# SmartSwitch_V1_1.net
KiCad netlist of a schematic drawn in EAGLE
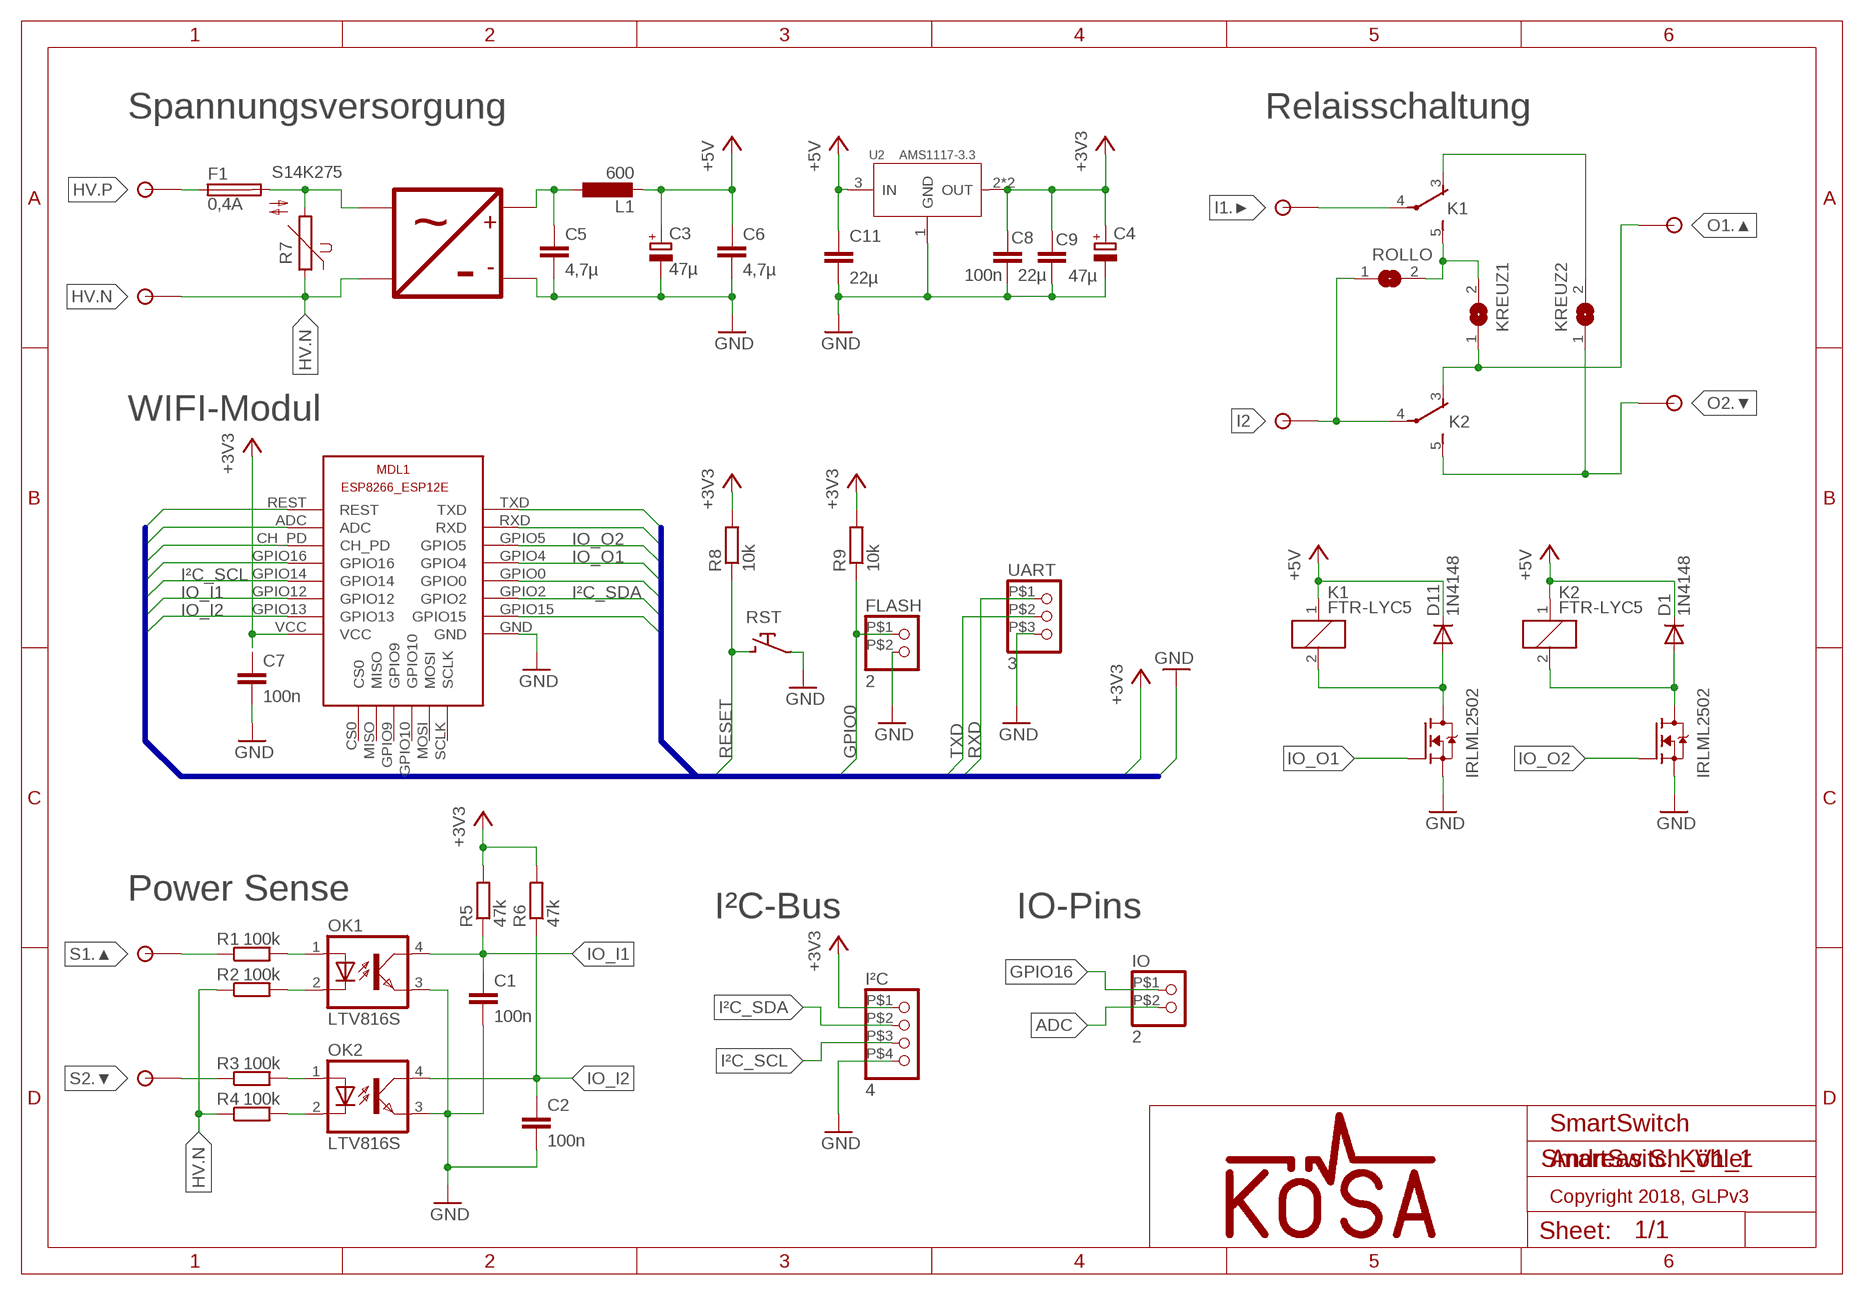
[diagram p0: schematic, sheet 1]

(export (version "E")
  (design (tool "Eeschema 10.0.6"))
  (components
    (comp (ref "C1")
      (value "100n")
      (footprint "eagle-import:C0805")
      (libsource (lib "eagle-import") (part "C-EUC0805"))
    )
    (comp (ref "C2")
      (value "100n")
      (footprint "eagle-import:C0805")
      (libsource (lib "eagle-import") (part "C-EUC0805"))
    )
    (comp (ref "C3")
      (value "47µ")
      (footprint "eagle-import:E2-5")
      (libsource (lib "eagle-import") (part "CPOL-EUE2-5"))
    )
    (comp (ref "C4")
      (value "47µ")
      (footprint "eagle-import:E2-5")
      (libsource (lib "eagle-import") (part "CPOL-EUE2-5"))
    )
    (comp (ref "C5")
      (value "4,7µ")
      (footprint "eagle-import:C0805")
      (libsource (lib "eagle-import") (part "C-EUC0805"))
    )
    (comp (ref "C6")
      (value "4,7µ")
      (footprint "eagle-import:C0805")
      (libsource (lib "eagle-import") (part "C-EUC0805"))
    )
    (comp (ref "C7")
      (value "100n")
      (footprint "eagle-import:C0805")
      (libsource (lib "eagle-import") (part "C-EUC0805"))
    )
    (comp (ref "C8")
      (value "100n")
      (footprint "eagle-import:C0805")
      (libsource (lib "eagle-import") (part "C-EUC0805"))
    )
    (comp (ref "C9")
      (value "22µ")
      (footprint "eagle-import:C0805")
      (libsource (lib "eagle-import") (part "C-EUC0805"))
    )
    (comp (ref "C11")
      (value "22µ")
      (footprint "eagle-import:C0805")
      (libsource (lib "eagle-import") (part "C-EUC0805"))
    )
    (comp (ref "D1")
      (value "1N4148")
      (footprint "eagle-import:SOD323-W")
      (libsource (lib "eagle-import") (part "DIODE-SOD323-W"))
    )
    (comp (ref "D11")
      (value "1N4148")
      (footprint "eagle-import:SOD323-W")
      (libsource (lib "eagle-import") (part "DIODE-SOD323-W"))
    )
    (comp (ref "F1")
      (value "0,4A")
      (footprint "eagle-import:SMD_FUSE_HOLDER")
      (libsource (lib "eagle-import") (part "SMD_FUSE_HOLDER"))
    )
    (comp (ref "FLASH")
      (value "2")
      (footprint "eagle-import:1X02_SMALL")
      (libsource (lib "eagle-import") (part "PINHD-1X2SMALL"))
    )
    (comp (ref "IO")
      (value "2")
      (footprint "eagle-import:1X02_SMALL")
      (libsource (lib "eagle-import") (part "PINHD-1X2SMALL"))
    )
    (comp (ref "I²C")
      (value "4")
      (footprint "eagle-import:1X04_SMALL")
      (libsource (lib "eagle-import") (part "PINHD-1X4SMALL"))
    )
    (comp (ref "K1")
      (value "FTR-LYC5")
      (footprint "eagle-import:FTR-LYC")
      (libsource (lib "eagle-import") (part "FTR-LYC5"))
    )
    (comp (ref "K2")
      (value "FTR-LYC5")
      (footprint "eagle-import:FTR-LYC")
      (libsource (lib "eagle-import") (part "FTR-LYC5"))
    )
    (comp (ref "KREUZ1")
      (value "SJW")
      (footprint "eagle-import:SJW")
      (libsource (lib "eagle-import") (part "SJW"))
    )
    (comp (ref "KREUZ2")
      (value "SJW")
      (footprint "eagle-import:SJW")
      (libsource (lib "eagle-import") (part "SJW"))
    )
    (comp (ref "L1")
      (value "600")
      (footprint "eagle-import:L3225P")
      (libsource (lib "eagle-import") (part "L-EUL3225P"))
    )
    (comp (ref "MDL1")
      (value "1")
      (footprint "eagle-import:ESP8266-ESP12E")
      (libsource (lib "eagle-import") (part "ESP8266-12EESP8266-ESP12E"))
    )
    (comp (ref "OK1")
      (value "LTV816S")
      (footprint "eagle-import:SMD4")
      (libsource (lib "eagle-import") (part "LTV816S"))
    )
    (comp (ref "OK2")
      (value "LTV816S")
      (footprint "eagle-import:SMD4")
      (libsource (lib "eagle-import") (part "LTV816S"))
    )
    (comp (ref "R1")
      (value "100k")
      (footprint "eagle-import:R1206")
      (libsource (lib "eagle-import") (part "R-EU_R1206"))
    )
    (comp (ref "R2")
      (value "100k")
      (footprint "eagle-import:R1206")
      (libsource (lib "eagle-import") (part "R-EU_R1206"))
    )
    (comp (ref "R3")
      (value "100k")
      (footprint "eagle-import:R1206")
      (libsource (lib "eagle-import") (part "R-EU_R1206"))
    )
    (comp (ref "R4")
      (value "100k")
      (footprint "eagle-import:R1206")
      (libsource (lib "eagle-import") (part "R-EU_R1206"))
    )
    (comp (ref "R5")
      (value "47k")
      (footprint "eagle-import:R1206")
      (libsource (lib "eagle-import") (part "R-EU_R1206"))
    )
    (comp (ref "R6")
      (value "47k")
      (footprint "eagle-import:R1206")
      (libsource (lib "eagle-import") (part "R-EU_R1206"))
    )
    (comp (ref "R7")
      (value "S14K275")
      (footprint "eagle-import:S14K275")
      (libsource (lib "eagle-import") (part "S14K275"))
    )
    (comp (ref "R8")
      (value "10k")
      (footprint "eagle-import:R1206")
      (libsource (lib "eagle-import") (part "R-EU_R1206"))
    )
    (comp (ref "R9")
      (value "10k")
      (footprint "eagle-import:R1206")
      (libsource (lib "eagle-import") (part "R-EU_R1206"))
    )
    (comp (ref "ROLLO")
      (value "SJW")
      (footprint "eagle-import:SJW")
      (libsource (lib "eagle-import") (part "SJW"))
    )
    (comp (ref "RST")
      (value "SMD-TASTER_REICHELT_KMR_231_G_LFS")
      (footprint "eagle-import:SMD-TASTER_REICHELT_KMR_231_G_LFS")
      (libsource (lib "eagle-import") (part "SMD-TASTER_REICHELT_KMR_231_G_LFS"))
    )
    (comp (ref "U$1")
      (value "HLK-PM01")
      (footprint "eagle-import:HLK-PM01")
      (libsource (lib "eagle-import") (part "HLK-PM01"))
    )
    (comp (ref "U$2")
      (value "RND_205-00276")
      (footprint "eagle-import:RND205-00276")
      (libsource (lib "eagle-import") (part "RND_205-00276"))
    )
    (comp (ref "U$3")
      (value "RND_205-00276")
      (footprint "eagle-import:RND205-00276")
      (libsource (lib "eagle-import") (part "RND_205-00276"))
    )
    (comp (ref "U$4")
      (value "RND_205-00276")
      (footprint "eagle-import:RND205-00276")
      (libsource (lib "eagle-import") (part "RND_205-00276"))
    )
    (comp (ref "U$5")
      (value "RND_205-00276")
      (footprint "eagle-import:RND205-00276")
      (libsource (lib "eagle-import") (part "RND_205-00276"))
    )
    (comp (ref "U$7")
      (value "IRLML2502")
      (footprint "eagle-import:SOT23")
      (libsource (lib "eagle-import") (part "IRLML2502"))
    )
    (comp (ref "U$8")
      (value "IRLML2502")
      (footprint "eagle-import:SOT23")
      (libsource (lib "eagle-import") (part "IRLML2502"))
    )
    (comp (ref "U2")
      (value "AMS1117-3.3")
      (footprint "eagle-import:SOT-223")
      (fields (field (name "MPN") "CJT1117-3.3"))
      (libsource (lib "eagle-import") (part "PMIC-CJT1117-3.3(SOT223)"))
    )
    (comp (ref "UART")
      (value "3")
      (footprint "eagle-import:1X03_SMALL")
      (libsource (lib "eagle-import") (part "PINHD-1X3SMALL"))
    )
  )
  (nets
    (net (code "1") (name "+3V3") (class "Default")
      (node (ref "C4") (pin "+") (pinfunction "+_+") (pintype "passive"))
      (node (ref "C7") (pin "1") (pinfunction "1_1") (pintype "passive"))
      (node (ref "C8") (pin "1") (pinfunction "1_1") (pintype "passive"))
      (node (ref "C9") (pin "1") (pinfunction "1_1") (pintype "passive"))
      (node (ref "I²C") (pin "P$1") (pinfunction "1_P$1") (pintype "passive"))
      (node (ref "MDL1") (pin "CH_PD") (pinfunction "CH_PD_CH_PD") (pintype "bidirectional"))
      (node (ref "MDL1") (pin "VCC") (pinfunction "VCC_VCC") (pintype "bidirectional"))
      (node (ref "R5") (pin "2") (pinfunction "2_2") (pintype "passive"))
      (node (ref "R6") (pin "2") (pinfunction "2_2") (pintype "passive"))
      (node (ref "R8") (pin "2") (pinfunction "2_2") (pintype "passive"))
      (node (ref "R9") (pin "2") (pinfunction "2_2") (pintype "passive"))
      (node (ref "U2") (pin "2") (pinfunction "OUT_2") (pintype "bidirectional"))
      (node (ref "U2") (pin "TER") (pinfunction "OUT_TER") (pintype "bidirectional"))
    )
    (net (code "2") (name "+5V") (class "Default")
      (node (ref "C11") (pin "1") (pinfunction "1_1") (pintype "passive"))
      (node (ref "C3") (pin "+") (pinfunction "+_+") (pintype "passive"))
      (node (ref "C6") (pin "1") (pinfunction "1_1") (pintype "passive"))
      (node (ref "D1") (pin "C") (pinfunction "C_C") (pintype "passive"))
      (node (ref "D11") (pin "C") (pinfunction "C_C") (pintype "passive"))
      (node (ref "K1") (pin "1") (pinfunction "1_1") (pintype "passive"))
      (node (ref "K2") (pin "1") (pinfunction "1_1") (pintype "passive"))
      (node (ref "L1") (pin "2") (pinfunction "2_2") (pintype "passive"))
      (node (ref "U2") (pin "3") (pinfunction "IN_3") (pintype "bidirectional"))
    )
    (net (code "3") (name "/GPIO0") (class "Default")
      (node (ref "FLASH") (pin "P$1") (pinfunction "1_P$1") (pintype "passive"))
      (node (ref "MDL1") (pin "GPIO0") (pinfunction "GPIO0_GPIO0") (pintype "bidirectional"))
      (node (ref "R9") (pin "1") (pinfunction "1_1") (pintype "passive"))
    )
    (net (code "4") (name "/RESET") (class "Default")
      (node (ref "MDL1") (pin "REST") (pinfunction "REST_REST") (pintype "bidirectional"))
      (node (ref "R8") (pin "1") (pinfunction "1_1") (pintype "passive"))
      (node (ref "RST") (pin "2_1") (pinfunction "B_2_1") (pintype "bidirectional"))
      (node (ref "RST") (pin "2_2") (pinfunction "B_2_2") (pintype "bidirectional"))
    )
    (net (code "5") (name "/RXD") (class "Default")
      (node (ref "MDL1") (pin "RXD") (pinfunction "RXD_RXD") (pintype "bidirectional"))
      (node (ref "UART") (pin "P$1") (pinfunction "1_P$1") (pintype "passive"))
    )
    (net (code "6") (name "/TXD") (class "Default")
      (node (ref "MDL1") (pin "TXD") (pinfunction "TXD_TXD") (pintype "bidirectional"))
      (node (ref "UART") (pin "P$2") (pinfunction "2_P$2") (pintype "passive"))
    )
    (net (code "7") (name "ADC") (class "Default")
      (node (ref "IO") (pin "P$2") (pinfunction "2_P$2") (pintype "passive"))
      (node (ref "MDL1") (pin "ADC") (pinfunction "ADC_ADC") (pintype "bidirectional"))
    )
    (net (code "8") (name "GND") (class "Default")
      (node (ref "C1") (pin "2") (pinfunction "2_2") (pintype "passive"))
      (node (ref "C11") (pin "2") (pinfunction "2_2") (pintype "passive"))
      (node (ref "C2") (pin "2") (pinfunction "2_2") (pintype "passive"))
      (node (ref "C3") (pin "-") (pinfunction "-_-") (pintype "passive"))
      (node (ref "C4") (pin "-") (pinfunction "-_-") (pintype "passive"))
      (node (ref "C5") (pin "2") (pinfunction "2_2") (pintype "passive"))
      (node (ref "C6") (pin "2") (pinfunction "2_2") (pintype "passive"))
      (node (ref "C7") (pin "2") (pinfunction "2_2") (pintype "passive"))
      (node (ref "C8") (pin "2") (pinfunction "2_2") (pintype "passive"))
      (node (ref "C9") (pin "2") (pinfunction "2_2") (pintype "passive"))
      (node (ref "FLASH") (pin "P$2") (pinfunction "2_P$2") (pintype "passive"))
      (node (ref "I²C") (pin "P$4") (pinfunction "4_P$4") (pintype "passive"))
      (node (ref "MDL1") (pin "GND") (pinfunction "GND_GND") (pintype "bidirectional"))
      (node (ref "MDL1") (pin "GPIO15") (pinfunction "GPIO15_GPIO15") (pintype "bidirectional"))
      (node (ref "OK1") (pin "3") (pinfunction "EMIT_3") (pintype "passive"))
      (node (ref "OK2") (pin "3") (pinfunction "EMIT_3") (pintype "passive"))
      (node (ref "RST") (pin "1_1") (pinfunction "A_1_1") (pintype "bidirectional"))
      (node (ref "RST") (pin "1_2") (pinfunction "A_1_2") (pintype "bidirectional"))
      (node (ref "U$1") (pin "DC-") (pinfunction "DC-_DC-") (pintype "power_in"))
      (node (ref "U$7") (pin "2") (pinfunction "S_2") (pintype "passive"))
      (node (ref "U$8") (pin "2") (pinfunction "S_2") (pintype "passive"))
      (node (ref "U2") (pin "1") (pinfunction "GND_1") (pintype "bidirectional"))
      (node (ref "UART") (pin "P$3") (pinfunction "3_P$3") (pintype "passive"))
    )
    (net (code "9") (name "GPIO16") (class "Default")
      (node (ref "IO") (pin "P$1") (pinfunction "1_P$1") (pintype "passive"))
      (node (ref "MDL1") (pin "GPIO16") (pinfunction "GPIO16_GPIO16") (pintype "bidirectional"))
    )
    (net (code "10") (name "HV.N") (class "Default")
      (node (ref "R2") (pin "1") (pinfunction "1_1") (pintype "passive"))
      (node (ref "R4") (pin "1") (pinfunction "1_1") (pintype "passive"))
      (node (ref "R7") (pin "1") (pinfunction "1_1") (pintype "passive"))
      (node (ref "U$1") (pin "AC2") (pinfunction "AC2_AC2") (pintype "power_in"))
      (node (ref "U$2") (pin "P$2") (pinfunction "P$1_P$2") (pintype "bidirectional"))
    )
    (net (code "11") (name "HV.P") (class "Default")
      (node (ref "F1") (pin "P$1") (pinfunction "1_P$1") (pintype "passive"))
      (node (ref "U$2") (pin "P$1") (pinfunction "P$1_P$1") (pintype "bidirectional"))
    )
    (net (code "12") (name "I1.►") (class "Default")
      (node (ref "K1") (pin "4") (pinfunction "P_4") (pintype "passive"))
      (node (ref "U$4") (pin "P$1") (pinfunction "P$1_P$1") (pintype "bidirectional"))
    )
    (net (code "13") (name "I2") (class "Default")
      (node (ref "K2") (pin "4") (pinfunction "P_4") (pintype "passive"))
      (node (ref "ROLLO") (pin "1") (pinfunction "1_1") (pintype "passive"))
      (node (ref "U$3") (pin "P$1") (pinfunction "P$1_P$1") (pintype "bidirectional"))
    )
    (net (code "14") (name "IO_I1") (class "Default")
      (node (ref "C1") (pin "1") (pinfunction "1_1") (pintype "passive"))
      (node (ref "MDL1") (pin "GPIO12") (pinfunction "GPIO12_GPIO12") (pintype "bidirectional"))
      (node (ref "OK1") (pin "4") (pinfunction "COL_4") (pintype "passive"))
      (node (ref "R5") (pin "1") (pinfunction "1_1") (pintype "passive"))
    )
    (net (code "15") (name "IO_I2") (class "Default")
      (node (ref "C2") (pin "1") (pinfunction "1_1") (pintype "passive"))
      (node (ref "MDL1") (pin "GPIO13") (pinfunction "GPIO13_GPIO13") (pintype "bidirectional"))
      (node (ref "OK2") (pin "4") (pinfunction "COL_4") (pintype "passive"))
      (node (ref "R6") (pin "1") (pinfunction "1_1") (pintype "passive"))
    )
    (net (code "16") (name "IO_O1") (class "Default")
      (node (ref "MDL1") (pin "GPIO4") (pinfunction "GPIO4_GPIO4") (pintype "bidirectional"))
      (node (ref "U$7") (pin "1") (pinfunction "G_1") (pintype "passive"))
    )
    (net (code "17") (name "IO_O2") (class "Default")
      (node (ref "MDL1") (pin "GPIO5") (pinfunction "GPIO5_GPIO5") (pintype "bidirectional"))
      (node (ref "U$8") (pin "1") (pinfunction "G_1") (pintype "passive"))
    )
    (net (code "18") (name "I²C_SCL") (class "Default")
      (node (ref "I²C") (pin "P$3") (pinfunction "3_P$3") (pintype "passive"))
      (node (ref "MDL1") (pin "GPIO14") (pinfunction "GPIO14_GPIO14") (pintype "bidirectional"))
    )
    (net (code "19") (name "I²C_SDA") (class "Default")
      (node (ref "I²C") (pin "P$2") (pinfunction "2_P$2") (pintype "passive"))
      (node (ref "MDL1") (pin "GPIO2") (pinfunction "GPIO2_GPIO2") (pintype "bidirectional"))
    )
    (net (code "20") (name "Net-(C5-Pad1)") (class "Default")
      (node (ref "C5") (pin "1") (pinfunction "1_1") (pintype "passive"))
      (node (ref "L1") (pin "1") (pinfunction "1_1") (pintype "passive"))
      (node (ref "U$1") (pin "DC+") (pinfunction "DC+_DC+") (pintype "power_in"))
    )
    (net (code "21") (name "Net-(F1-2)") (class "Default")
      (node (ref "F1") (pin "P$2") (pinfunction "2_P$2") (pintype "passive"))
      (node (ref "R7") (pin "2") (pinfunction "2_2") (pintype "passive"))
      (node (ref "U$1") (pin "AC1") (pinfunction "AC1_AC1") (pintype "power_in"))
    )
    (net (code "22") (name "Net-(K1A-O)") (class "Default")
      (node (ref "K1") (pin "3") (pinfunction "O_3") (pintype "passive"))
      (node (ref "KREUZ2") (pin "2") (pinfunction "2_2") (pintype "passive"))
    )
    (net (code "23") (name "Net-(K1A-S)") (class "Default")
      (node (ref "K1") (pin "5") (pinfunction "S_5") (pintype "passive"))
      (node (ref "KREUZ1") (pin "2") (pinfunction "2_2") (pintype "passive"))
      (node (ref "ROLLO") (pin "2") (pinfunction "2_2") (pintype "passive"))
    )
    (net (code "24") (name "Net-(OK1-A)") (class "Default")
      (node (ref "OK1") (pin "1") (pinfunction "A_1") (pintype "passive"))
      (node (ref "R1") (pin "2") (pinfunction "2_2") (pintype "passive"))
    )
    (net (code "25") (name "Net-(OK1-C)") (class "Default")
      (node (ref "OK1") (pin "2") (pinfunction "C_2") (pintype "passive"))
      (node (ref "R2") (pin "2") (pinfunction "2_2") (pintype "passive"))
    )
    (net (code "26") (name "Net-(OK2-A)") (class "Default")
      (node (ref "OK2") (pin "1") (pinfunction "A_1") (pintype "passive"))
      (node (ref "R3") (pin "2") (pinfunction "2_2") (pintype "passive"))
    )
    (net (code "27") (name "Net-(OK2-C)") (class "Default")
      (node (ref "OK2") (pin "2") (pinfunction "C_2") (pintype "passive"))
      (node (ref "R4") (pin "2") (pinfunction "2_2") (pintype "passive"))
    )
    (net (code "28") (name "Net-(U$7-D)") (class "Default")
      (node (ref "D11") (pin "A") (pinfunction "A_A") (pintype "passive"))
      (node (ref "K1") (pin "2") (pinfunction "2_2") (pintype "passive"))
      (node (ref "U$7") (pin "3") (pinfunction "D_3") (pintype "passive"))
    )
    (net (code "29") (name "Net-(U$8-D)") (class "Default")
      (node (ref "D1") (pin "A") (pinfunction "A_A") (pintype "passive"))
      (node (ref "K2") (pin "2") (pinfunction "2_2") (pintype "passive"))
      (node (ref "U$8") (pin "3") (pinfunction "D_3") (pintype "passive"))
    )
    (net (code "30") (name "O1.▲") (class "Default")
      (node (ref "K2") (pin "3") (pinfunction "O_3") (pintype "passive"))
      (node (ref "KREUZ1") (pin "1") (pinfunction "1_1") (pintype "passive"))
      (node (ref "U$3") (pin "P$2") (pinfunction "P$1_P$2") (pintype "bidirectional"))
    )
    (net (code "31") (name "O2.▼") (class "Default")
      (node (ref "K2") (pin "5") (pinfunction "S_5") (pintype "passive"))
      (node (ref "KREUZ2") (pin "1") (pinfunction "1_1") (pintype "passive"))
      (node (ref "U$4") (pin "P$2") (pinfunction "P$1_P$2") (pintype "bidirectional"))
    )
    (net (code "32") (name "S1.▲") (class "Default")
      (node (ref "R1") (pin "1") (pinfunction "1_1") (pintype "passive"))
      (node (ref "U$5") (pin "P$2") (pinfunction "P$1_P$2") (pintype "bidirectional"))
    )
    (net (code "33") (name "S2.▼") (class "Default")
      (node (ref "R3") (pin "1") (pinfunction "1_1") (pintype "passive"))
      (node (ref "U$5") (pin "P$1") (pinfunction "P$1_P$1") (pintype "bidirectional"))
    )
    (net (code "34") (name "unconnected-(MDL1-PadCS0)") (class "Default")
      (node (ref "MDL1") (pin "CS0") (pinfunction "CS0_CS0") (pintype "bidirectional"))
    )
    (net (code "35") (name "unconnected-(MDL1-PadGPIO9)") (class "Default")
      (node (ref "MDL1") (pin "GPIO9") (pinfunction "GPIO9_GPIO9") (pintype "bidirectional"))
    )
    (net (code "36") (name "unconnected-(MDL1-PadGPIO10)") (class "Default")
      (node (ref "MDL1") (pin "GPIO10") (pinfunction "GPIO10_GPIO10") (pintype "bidirectional"))
    )
    (net (code "37") (name "unconnected-(MDL1-PadMISO)") (class "Default")
      (node (ref "MDL1") (pin "MISO") (pinfunction "MISO_MISO") (pintype "bidirectional"))
    )
    (net (code "38") (name "unconnected-(MDL1-PadMOSI)") (class "Default")
      (node (ref "MDL1") (pin "MOSI") (pinfunction "MOSI_MOSI") (pintype "bidirectional"))
    )
    (net (code "39") (name "unconnected-(MDL1-PadSCLK)") (class "Default")
      (node (ref "MDL1") (pin "SCLK") (pinfunction "SCLK_SCLK") (pintype "bidirectional"))
    )
  )
)
